# Headers-DESKTOP-L9L0IAD.net
KiCad netlist of a schematic drawn in Altium Designer
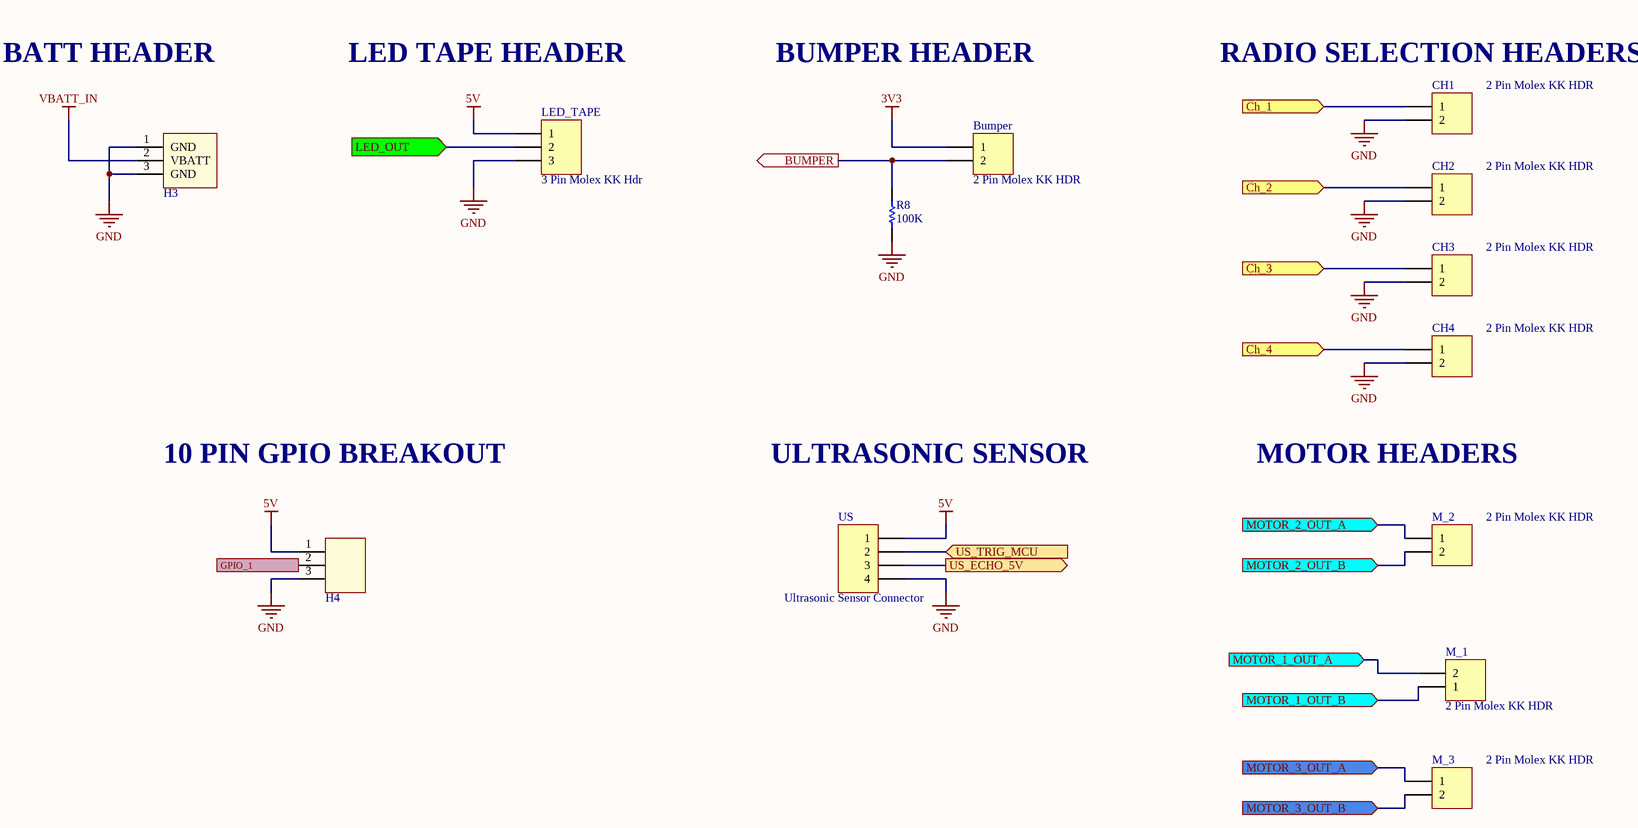
[diagram p0: Headers-DESKTOP-L9L0IAD.SchDoc]

(export (version "E")
  (design (tool "Eeschema 10.0.6"))
  (components
    (comp (ref "Bumper")
      (value "2 Pin Molex KK HDR")
      (footprint "MOLEX_KK_2_HDR")
      (description "CONN HEADER 2POS 2.54mm VERT_Thru Hole")
      (libsource (lib "ECE AD19Components_19V1") (part "JA_MOLEX_KK_2POS"))
    )
    (comp (ref "CH1")
      (value "2 Pin Molex KK HDR")
      (footprint "MOLEX_KK_2_HDR")
      (description "CONN HEADER 2POS 2.54mm VERT_Thru Hole")
      (libsource (lib "ECE AD19Components_19V1") (part "JA_MOLEX_KK_2POS"))
    )
    (comp (ref "CH2")
      (value "2 Pin Molex KK HDR")
      (footprint "MOLEX_KK_2_HDR")
      (description "CONN HEADER 2POS 2.54mm VERT_Thru Hole")
      (libsource (lib "ECE AD19Components_19V1") (part "JA_MOLEX_KK_2POS"))
    )
    (comp (ref "CH3")
      (value "2 Pin Molex KK HDR")
      (footprint "MOLEX_KK_2_HDR")
      (description "CONN HEADER 2POS 2.54mm VERT_Thru Hole")
      (libsource (lib "ECE AD19Components_19V1") (part "JA_MOLEX_KK_2POS"))
    )
    (comp (ref "CH4")
      (value "2 Pin Molex KK HDR")
      (footprint "MOLEX_KK_2_HDR")
      (description "CONN HEADER 2POS 2.54mm VERT_Thru Hole")
      (libsource (lib "ECE AD19Components_19V1") (part "JA_MOLEX_KK_2POS"))
    )
    (comp (ref "H3")
      (value "Battery_HEADER_3pin")
      (footprint "BATT_HEADER_3POS")
      (description "3Pin Header 2.54mm spacing")
      (libsource (lib "ENCE461AD19_19V2") (part "Battery_HEADER_3pin"))
    )
    (comp (ref "H4")
      (value "HEADER_3")
      (footprint "HEADER_3POS")
      (description "3Pin Header 2.54mm spacing")
      (libsource (lib "ENCE461AD19_19V2") (part "HEADER_3"))
    )
    (comp (ref "LED_TAPE")
      (value "3 Pin Molex KK Hdr")
      (footprint "MOLEX_KK_3_HDR")
      (description "CONN HEADER 3POS 2.54mm VERT_Thru Hole")
      (fields (field (name "MANUFACTURER") "Molex"))
      (libsource (lib "ECE AD19Components_19V1") (part "JA_MOLEX_KK_3POS"))
    )
    (comp (ref "M_1")
      (value "2 Pin Molex KK HDR")
      (footprint "MOLEX_KK_2_HDR")
      (description "CONN HEADER 2POS 2.54mm VERT_Thru Hole")
      (libsource (lib "") (part "JA_MOLEX_KK_2POS_1"))
    )
    (comp (ref "M_2")
      (value "2 Pin Molex KK HDR")
      (footprint "MOLEX_KK_2_HDR")
      (description "CONN HEADER 2POS 2.54mm VERT_Thru Hole")
      (libsource (lib "ECE AD19Components_19V1") (part "JA_MOLEX_KK_2POS"))
    )
    (comp (ref "M_3")
      (value "2 Pin Molex KK HDR")
      (footprint "MOLEX_KK_2_HDR")
      (description "CONN HEADER 2POS 2.54mm VERT_Thru Hole")
      (libsource (lib "ECE AD19Components_19V1") (part "JA_MOLEX_KK_2POS"))
    )
    (comp (ref "R8")
      (value "100K")
      (footprint "RESC1608L")
      (description "RES 100K OHM 1/10W 5% 0603 SMD")
      (libsource (lib "ECE AD19Components_19V1") (part "RS_100K"))
    )
    (comp (ref "US")
      (value "Ultrasonic Sensor Connector")
      (footprint "MOLEX_KK_4_HDR")
      (description "CONN HEADER 4POS 2.54mm VERT_Thru Hole")
      (fields (field (name "MANUFACTURER") "Molex"))
      (libsource (lib "ECE AD19Components_19V1") (part "JA_MOLEX_KK_4POS"))
    )
  )
  (nets
    (net (code "2") (name "/BUMPER") (class "Default")
      (node (ref "Bumper") (pin "2") (pinfunction "2_2") (pintype "passive"))
      (node (ref "R8") (pin "2") (pinfunction "2_2") (pintype "passive"))
    )
    (net (code "3") (name "/Ch_1") (class "Default")
      (node (ref "CH1") (pin "1") (pinfunction "1_1") (pintype "passive"))
    )
    (net (code "4") (name "/Ch_2") (class "Default")
      (node (ref "CH2") (pin "1") (pinfunction "1_1") (pintype "passive"))
    )
    (net (code "5") (name "/Ch_3") (class "Default")
      (node (ref "CH3") (pin "1") (pinfunction "1_1") (pintype "passive"))
    )
    (net (code "6") (name "/Ch_4") (class "Default")
      (node (ref "CH4") (pin "1") (pinfunction "1_1") (pintype "passive"))
    )
    (net (code "7") (name "/GPIO_1") (class "Default") (node (ref "H4") (pin "2") (pintype "passive")))
    (net (code "8") (name "/LED_OUT") (class "Default")
      (node (ref "LED_TAPE") (pin "2") (pinfunction "2_2") (pintype "passive"))
    )
    (net (code "9") (name "/MOTOR_1_OUT_A") (class "Default")
      (node (ref "M_1") (pin "2") (pinfunction "2_2") (pintype "passive"))
    )
    (net (code "10") (name "/MOTOR_1_OUT_B") (class "Default")
      (node (ref "M_1") (pin "1") (pinfunction "1_1") (pintype "passive"))
    )
    (net (code "11") (name "/MOTOR_2_OUT_A") (class "Default")
      (node (ref "M_2") (pin "1") (pinfunction "1_1") (pintype "passive"))
    )
    (net (code "12") (name "/MOTOR_2_OUT_B") (class "Default")
      (node (ref "M_2") (pin "2") (pinfunction "2_2") (pintype "passive"))
    )
    (net (code "13") (name "/MOTOR_3_OUT_A") (class "Default")
      (node (ref "M_3") (pin "1") (pinfunction "1_1") (pintype "passive"))
    )
    (net (code "14") (name "/MOTOR_3_OUT_B") (class "Default")
      (node (ref "M_3") (pin "2") (pinfunction "2_2") (pintype "passive"))
    )
    (net (code "15") (name "/US_ECHO_5V") (class "Default")
      (node (ref "US") (pin "3") (pinfunction "3_3") (pintype "passive"))
    )
    (net (code "16") (name "/US_TRIG_MCU") (class "Default")
      (node (ref "US") (pin "2") (pinfunction "2_2") (pintype "passive"))
    )
    (net (code "17") (name "3V3") (class "Default")
      (node (ref "Bumper") (pin "1") (pinfunction "1_1") (pintype "passive"))
    )
    (net (code "18") (name "5V") (class "Default")
      (node (ref "H4") (pin "1") (pintype "passive"))
      (node (ref "LED_TAPE") (pin "1") (pinfunction "1_1") (pintype "passive"))
      (node (ref "US") (pin "1") (pinfunction "1_1") (pintype "passive"))
    )
    (net (code "19") (name "GND") (class "Default")
      (node (ref "CH1") (pin "2") (pinfunction "2_2") (pintype "passive"))
      (node (ref "CH2") (pin "2") (pinfunction "2_2") (pintype "passive"))
      (node (ref "CH3") (pin "2") (pinfunction "2_2") (pintype "passive"))
      (node (ref "CH4") (pin "2") (pinfunction "2_2") (pintype "passive"))
      (node (ref "H3") (pin "1") (pinfunction "GND_1") (pintype "passive"))
      (node (ref "H3") (pin "3") (pinfunction "GND_3") (pintype "passive"))
      (node (ref "H4") (pin "3") (pintype "passive"))
      (node (ref "LED_TAPE") (pin "3") (pinfunction "3_3") (pintype "passive"))
      (node (ref "R8") (pin "1") (pinfunction "1_1") (pintype "passive"))
      (node (ref "US") (pin "4") (pinfunction "4_4") (pintype "passive"))
    )
    (net (code "20") (name "VBATT_IN") (class "Default")
      (node (ref "H3") (pin "2") (pinfunction "VBATT_2") (pintype "passive"))
    )
  )
)
